# LP55231_breakout.net
KiCad netlist of a schematic drawn in EAGLE
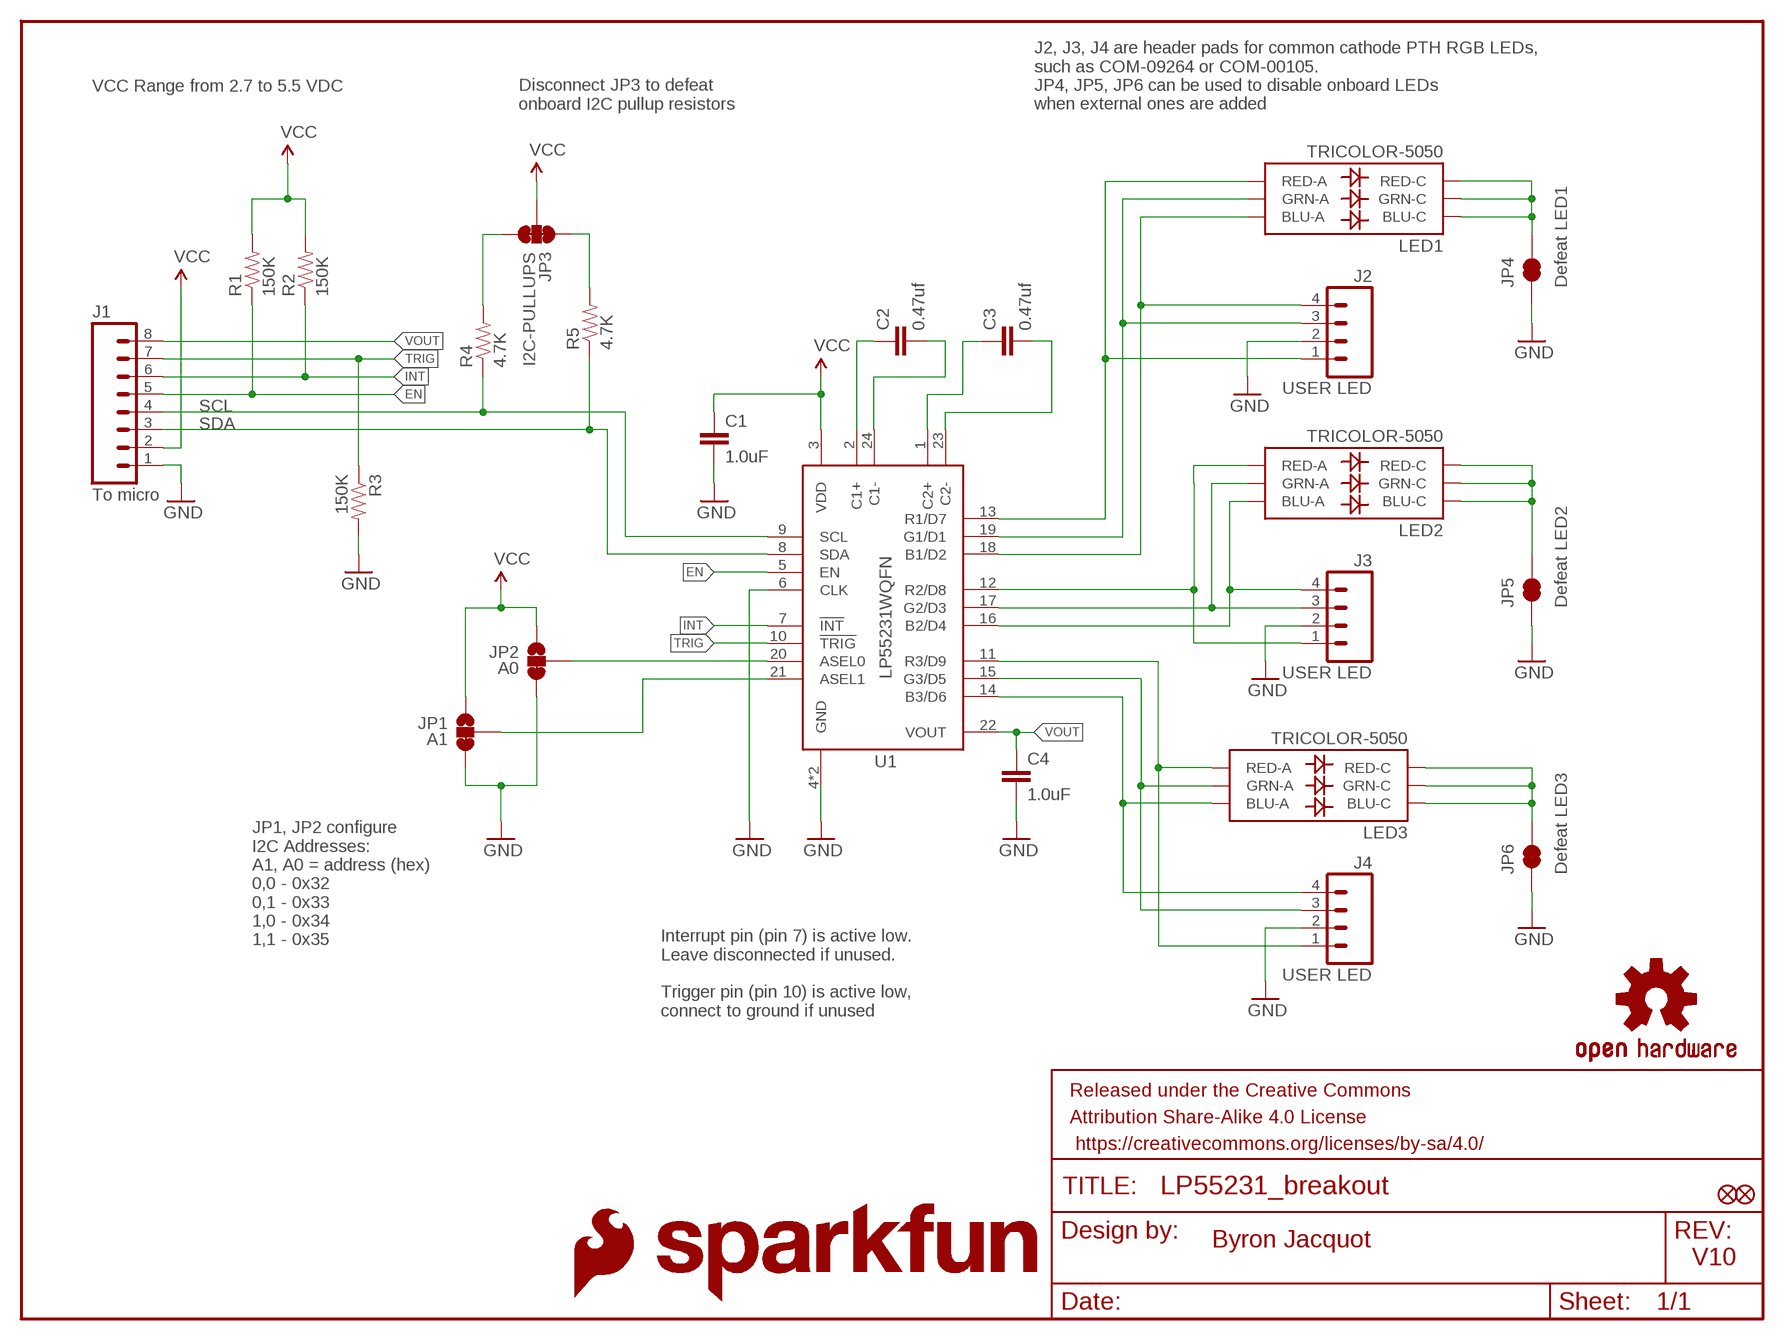
[diagram p0: schematic, sheet 1]

(export (version "E")
  (design (tool "Eeschema 10.0.6"))
  (components
    (comp (ref "C1")
      (value "1.0uF")
      (footprint "eagle-import:0603-CAP")
      (libsource (lib "eagle-import") (part "1.0UF-16V-10%(0603)"))
    )
    (comp (ref "C2")
      (value "0.47uf")
      (footprint "eagle-import:0603-CAP")
      (libsource (lib "eagle-import") (part "CAP0603-CAP"))
    )
    (comp (ref "C3")
      (value "0.47uf")
      (footprint "eagle-import:0603-CAP")
      (libsource (lib "eagle-import") (part "CAP0603-CAP"))
    )
    (comp (ref "C4")
      (value "1.0uF")
      (footprint "eagle-import:0603-CAP")
      (libsource (lib "eagle-import") (part "1.0UF-16V-10%(0603)"))
    )
    (comp (ref "FD1")
      (value "FIDUCIALUFIDUCIAL")
      (footprint "eagle-import:MICRO-FIDUCIAL")
      (libsource (lib "eagle-import") (part "FIDUCIALUFIDUCIAL"))
    )
    (comp (ref "FD2")
      (value "FIDUCIALUFIDUCIAL")
      (footprint "eagle-import:MICRO-FIDUCIAL")
      (libsource (lib "eagle-import") (part "FIDUCIALUFIDUCIAL"))
    )
    (comp (ref "FRAME1")
      (value "FRAME-LETTER")
      (footprint "eagle-import:CREATIVE_COMMONS")
      (libsource (lib "eagle-import") (part "FRAME-LETTER"))
    )
    (comp (ref "J1")
      (value "To micro")
      (footprint "eagle-import:1X08_NO_SILK")
      (libsource (lib "eagle-import") (part "M08NO_SILK_FEMALE_PTH"))
    )
    (comp (ref "J2")
      (value "USER LED")
      (footprint "eagle-import:1X04_NO_SILK_ALL_ROUND")
      (libsource (lib "eagle-import") (part "M04NO_SILK_ALL_ROUND"))
    )
    (comp (ref "J3")
      (value "USER LED")
      (footprint "eagle-import:1X04_NO_SILK_ALL_ROUND")
      (libsource (lib "eagle-import") (part "M04NO_SILK_ALL_ROUND"))
    )
    (comp (ref "J4")
      (value "USER LED")
      (footprint "eagle-import:1X04_NO_SILK_ALL_ROUND")
      (libsource (lib "eagle-import") (part "M04NO_SILK_ALL_ROUND"))
    )
    (comp (ref "JP1")
      (value "A1")
      (footprint "eagle-import:PAD-JUMPER-3-2OF3_NC_BY_TRACE_YES_SILK_FULL_BOX")
      (libsource (lib "eagle-import") (part "JUMPER-PAD-3-2OF3_NC_BY_TRACE_SMALL"))
    )
    (comp (ref "JP2")
      (value "A0")
      (footprint "eagle-import:PAD-JUMPER-3-2OF3_NC_BY_TRACE_YES_SILK_FULL_BOX")
      (libsource (lib "eagle-import") (part "JUMPER-PAD-3-2OF3_NC_BY_TRACE_SMALL"))
    )
    (comp (ref "JP3")
      (value "I2C-PULLUPS")
      (footprint "eagle-import:PAD-JUMPER-3-3OF3_NC_BY_TRACE_YES_SILK_FULL_BOX")
      (libsource (lib "eagle-import") (part "JUMPER-PAD-3-NC_BY_TRACE"))
    )
    (comp (ref "JP4")
      (value "Defeat LED1")
      (footprint "eagle-import:PAD-JUMPER-2-NC_BY_TRACE_NO_SILK")
      (libsource (lib "eagle-import") (part "JUMPER-PAD-2-NC_BY_TRACENO_SILK"))
    )
    (comp (ref "JP5")
      (value "Defeat LED2")
      (footprint "eagle-import:PAD-JUMPER-2-NC_BY_TRACE_NO_SILK")
      (libsource (lib "eagle-import") (part "JUMPER-PAD-2-NC_BY_TRACENO_SILK"))
    )
    (comp (ref "JP6")
      (value "Defeat LED3")
      (footprint "eagle-import:PAD-JUMPER-2-NC_BY_TRACE_NO_SILK")
      (libsource (lib "eagle-import") (part "JUMPER-PAD-2-NC_BY_TRACENO_SILK"))
    )
    (comp (ref "LED1")
      (value "TRICOLOR-5050")
      (footprint "eagle-import:LED-TRICOLOR-5050")
      (libsource (lib "eagle-import") (part "LED-TRICOLOR-5050NO_IC"))
    )
    (comp (ref "LED2")
      (value "TRICOLOR-5050")
      (footprint "eagle-import:LED-TRICOLOR-5050")
      (libsource (lib "eagle-import") (part "LED-TRICOLOR-5050NO_IC"))
    )
    (comp (ref "LED3")
      (value "TRICOLOR-5050")
      (footprint "eagle-import:LED-TRICOLOR-5050")
      (libsource (lib "eagle-import") (part "LED-TRICOLOR-5050NO_IC"))
    )
    (comp (ref "LOGO1")
      (value "SFE_LOGO_FLAME.1_INCH")
      (footprint "eagle-import:SFE_LOGO_FLAME_.1")
      (libsource (lib "eagle-import") (part "SFE_LOGO_FLAME.1_INCH"))
    )
    (comp (ref "LOGO2")
      (value "SFE_LOGO_NAME.1_INCH")
      (footprint "eagle-import:SFE_LOGO_NAME_.1")
      (libsource (lib "eagle-import") (part "SFE_LOGO_NAME.1_INCH"))
    )
    (comp (ref "LOGO3")
      (value "OSHW-LOGOS")
      (footprint "eagle-import:OSHW-LOGO-S")
      (libsource (lib "eagle-import") (part "OSHW-LOGOS"))
    )
    (comp (ref "R1")
      (value "150K")
      (footprint "eagle-import:0603-RES")
      (libsource (lib "eagle-import") (part "150KOHM1/10W1%(0603)"))
    )
    (comp (ref "R2")
      (value "150K")
      (footprint "eagle-import:0603-RES")
      (libsource (lib "eagle-import") (part "150KOHM1/10W1%(0603)"))
    )
    (comp (ref "R3")
      (value "150K")
      (footprint "eagle-import:0603-RES")
      (libsource (lib "eagle-import") (part "150KOHM1/10W1%(0603)"))
    )
    (comp (ref "R4")
      (value "4.7K")
      (footprint "eagle-import:0603-RES")
      (libsource (lib "eagle-import") (part "4.7KOHM-1/10W-1%(0603)"))
    )
    (comp (ref "R5")
      (value "4.7K")
      (footprint "eagle-import:0603-RES")
      (libsource (lib "eagle-import") (part "4.7KOHM-1/10W-1%(0603)"))
    )
    (comp (ref "U1")
      (value "LP55231WQFN")
      (footprint "eagle-import:WQFN-24")
      (libsource (lib "eagle-import") (part "LP55231WQFN"))
    )
  )
  (nets
    (net (code "1") (name "/SCL") (class "Default")
      (node (ref "J1") (pin "4") (pinfunction "4_4") (pintype "passive"))
      (node (ref "R4") (pin "1") (pinfunction "1_1") (pintype "passive"))
      (node (ref "U1") (pin "9") (pinfunction "SCL_9") (pintype "bidirectional"))
    )
    (net (code "2") (name "/SDA") (class "Default")
      (node (ref "J1") (pin "3") (pinfunction "3_3") (pintype "passive"))
      (node (ref "R5") (pin "1") (pinfunction "1_1") (pintype "passive"))
      (node (ref "U1") (pin "8") (pinfunction "SDA_8") (pintype "bidirectional"))
    )
    (net (code "3") (name "EN") (class "Default")
      (node (ref "J1") (pin "5") (pinfunction "5_5") (pintype "passive"))
      (node (ref "R1") (pin "1") (pinfunction "1_1") (pintype "passive"))
      (node (ref "U1") (pin "5") (pinfunction "EN_5") (pintype "bidirectional"))
    )
    (net (code "4") (name "GND") (class "Default")
      (node (ref "C1") (pin "2") (pinfunction "2_2") (pintype "passive"))
      (node (ref "C4") (pin "2") (pinfunction "2_2") (pintype "passive"))
      (node (ref "J1") (pin "1") (pinfunction "1_1") (pintype "passive"))
      (node (ref "J2") (pin "2") (pinfunction "2_2") (pintype "passive"))
      (node (ref "J3") (pin "2") (pinfunction "2_2") (pintype "passive"))
      (node (ref "J4") (pin "2") (pinfunction "2_2") (pintype "passive"))
      (node (ref "JP1") (pin "3") (pinfunction "3_3") (pintype "passive"))
      (node (ref "JP2") (pin "3") (pinfunction "3_3") (pintype "passive"))
      (node (ref "JP4") (pin "1") (pinfunction "1_1") (pintype "passive"))
      (node (ref "JP5") (pin "1") (pinfunction "1_1") (pintype "passive"))
      (node (ref "JP6") (pin "1") (pinfunction "1_1") (pintype "passive"))
      (node (ref "R3") (pin "2") (pinfunction "2_2") (pintype "passive"))
      (node (ref "U1") (pin "4") (pinfunction "GND_4") (pintype "bidirectional"))
      (node (ref "U1") (pin "6") (pinfunction "CLK_6") (pintype "bidirectional"))
      (node (ref "U1") (pin "EP") (pinfunction "GND_EP") (pintype "bidirectional"))
    )
    (net (code "5") (name "INT") (class "Default")
      (node (ref "J1") (pin "6") (pinfunction "6_6") (pintype "passive"))
      (node (ref "R2") (pin "1") (pinfunction "1_1") (pintype "passive"))
      (node (ref "U1") (pin "7") (pinfunction "~{INT}_7") (pintype "bidirectional"))
    )
    (net (code "6") (name "Net-(JP3-Pad1)") (class "Default")
      (node (ref "JP3") (pin "1") (pinfunction "1_1") (pintype "passive"))
      (node (ref "R5") (pin "2") (pinfunction "2_2") (pintype "passive"))
    )
    (net (code "7") (name "Net-(JP3-Pad3)") (class "Default")
      (node (ref "JP3") (pin "3") (pinfunction "3_3") (pintype "passive"))
      (node (ref "R4") (pin "2") (pinfunction "2_2") (pintype "passive"))
    )
    (net (code "8") (name "Net-(LED1-BLU-A)") (class "Default")
      (node (ref "J2") (pin "4") (pinfunction "4_4") (pintype "passive"))
      (node (ref "LED1") (pin "3") (pinfunction "BLU-A_3") (pintype "bidirectional"))
      (node (ref "U1") (pin "18") (pinfunction "B1/D2_18") (pintype "bidirectional"))
    )
    (net (code "9") (name "Net-(LED1-BLU-C)") (class "Default")
      (node (ref "JP4") (pin "2") (pinfunction "2_2") (pintype "passive"))
      (node (ref "LED1") (pin "4") (pinfunction "BLU-C_4") (pintype "bidirectional"))
      (node (ref "LED1") (pin "5") (pinfunction "RED-C_5") (pintype "bidirectional"))
      (node (ref "LED1") (pin "6") (pinfunction "GRN-C_6") (pintype "bidirectional"))
    )
    (net (code "10") (name "Net-(LED1-GRN-A)") (class "Default")
      (node (ref "J2") (pin "3") (pinfunction "3_3") (pintype "passive"))
      (node (ref "LED1") (pin "1") (pinfunction "GRN-A_1") (pintype "bidirectional"))
      (node (ref "U1") (pin "19") (pinfunction "G1/D1_19") (pintype "bidirectional"))
    )
    (net (code "11") (name "Net-(LED1-RED-A)") (class "Default")
      (node (ref "J2") (pin "1") (pinfunction "1_1") (pintype "passive"))
      (node (ref "LED1") (pin "2") (pinfunction "RED-A_2") (pintype "bidirectional"))
      (node (ref "U1") (pin "13") (pinfunction "R1/D7_13") (pintype "bidirectional"))
    )
    (net (code "12") (name "Net-(LED2-BLU-A)") (class "Default")
      (node (ref "J3") (pin "4") (pinfunction "4_4") (pintype "passive"))
      (node (ref "LED2") (pin "3") (pinfunction "BLU-A_3") (pintype "bidirectional"))
      (node (ref "U1") (pin "16") (pinfunction "B2/D4_16") (pintype "bidirectional"))
    )
    (net (code "13") (name "Net-(LED2-BLU-C)") (class "Default")
      (node (ref "JP5") (pin "2") (pinfunction "2_2") (pintype "passive"))
      (node (ref "LED2") (pin "4") (pinfunction "BLU-C_4") (pintype "bidirectional"))
      (node (ref "LED2") (pin "5") (pinfunction "RED-C_5") (pintype "bidirectional"))
      (node (ref "LED2") (pin "6") (pinfunction "GRN-C_6") (pintype "bidirectional"))
    )
    (net (code "14") (name "Net-(LED2-GRN-A)") (class "Default")
      (node (ref "J3") (pin "3") (pinfunction "3_3") (pintype "passive"))
      (node (ref "LED2") (pin "1") (pinfunction "GRN-A_1") (pintype "bidirectional"))
      (node (ref "U1") (pin "17") (pinfunction "G2/D3_17") (pintype "bidirectional"))
    )
    (net (code "15") (name "Net-(LED2-RED-A)") (class "Default")
      (node (ref "J3") (pin "1") (pinfunction "1_1") (pintype "passive"))
      (node (ref "LED2") (pin "2") (pinfunction "RED-A_2") (pintype "bidirectional"))
      (node (ref "U1") (pin "12") (pinfunction "R2/D8_12") (pintype "bidirectional"))
    )
    (net (code "16") (name "Net-(LED3-BLU-A)") (class "Default")
      (node (ref "J4") (pin "4") (pinfunction "4_4") (pintype "passive"))
      (node (ref "LED3") (pin "3") (pinfunction "BLU-A_3") (pintype "bidirectional"))
      (node (ref "U1") (pin "14") (pinfunction "B3/D6_14") (pintype "bidirectional"))
    )
    (net (code "17") (name "Net-(LED3-BLU-C)") (class "Default")
      (node (ref "JP6") (pin "2") (pinfunction "2_2") (pintype "passive"))
      (node (ref "LED3") (pin "4") (pinfunction "BLU-C_4") (pintype "bidirectional"))
      (node (ref "LED3") (pin "5") (pinfunction "RED-C_5") (pintype "bidirectional"))
      (node (ref "LED3") (pin "6") (pinfunction "GRN-C_6") (pintype "bidirectional"))
    )
    (net (code "18") (name "Net-(LED3-GRN-A)") (class "Default")
      (node (ref "J4") (pin "3") (pinfunction "3_3") (pintype "passive"))
      (node (ref "LED3") (pin "1") (pinfunction "GRN-A_1") (pintype "bidirectional"))
      (node (ref "U1") (pin "15") (pinfunction "G3/D5_15") (pintype "bidirectional"))
    )
    (net (code "19") (name "Net-(LED3-RED-A)") (class "Default")
      (node (ref "J4") (pin "1") (pinfunction "1_1") (pintype "passive"))
      (node (ref "LED3") (pin "2") (pinfunction "RED-A_2") (pintype "bidirectional"))
      (node (ref "U1") (pin "11") (pinfunction "R3/D9_11") (pintype "bidirectional"))
    )
    (net (code "20") (name "Net-(U1-ASEL0)") (class "Default")
      (node (ref "JP2") (pin "2") (pinfunction "2_2") (pintype "passive"))
      (node (ref "U1") (pin "20") (pinfunction "ASEL0_20") (pintype "bidirectional"))
    )
    (net (code "21") (name "Net-(U1-ASEL1)") (class "Default")
      (node (ref "JP1") (pin "2") (pinfunction "2_2") (pintype "passive"))
      (node (ref "U1") (pin "21") (pinfunction "ASEL1_21") (pintype "bidirectional"))
    )
    (net (code "22") (name "Net-(U1-C1+)") (class "Default")
      (node (ref "C2") (pin "1") (pinfunction "1_1") (pintype "passive"))
      (node (ref "U1") (pin "2") (pinfunction "C1+_2") (pintype "bidirectional"))
    )
    (net (code "23") (name "Net-(U1-C1-)") (class "Default")
      (node (ref "C2") (pin "2") (pinfunction "2_2") (pintype "passive"))
      (node (ref "U1") (pin "24") (pinfunction "C1-_24") (pintype "bidirectional"))
    )
    (net (code "24") (name "Net-(U1-C2+)") (class "Default")
      (node (ref "C3") (pin "1") (pinfunction "1_1") (pintype "passive"))
      (node (ref "U1") (pin "1") (pinfunction "C2+_1") (pintype "bidirectional"))
    )
    (net (code "25") (name "Net-(U1-C2-)") (class "Default")
      (node (ref "C3") (pin "2") (pinfunction "2_2") (pintype "passive"))
      (node (ref "U1") (pin "23") (pinfunction "C2-_23") (pintype "bidirectional"))
    )
    (net (code "26") (name "TRIG") (class "Default")
      (node (ref "J1") (pin "7") (pinfunction "7_7") (pintype "passive"))
      (node (ref "R3") (pin "1") (pinfunction "1_1") (pintype "passive"))
      (node (ref "U1") (pin "10") (pinfunction "~{TRIG}_10") (pintype "bidirectional"))
    )
    (net (code "27") (name "VCC") (class "Default")
      (node (ref "C1") (pin "1") (pinfunction "1_1") (pintype "passive"))
      (node (ref "J1") (pin "2") (pinfunction "2_2") (pintype "passive"))
      (node (ref "JP1") (pin "1") (pinfunction "1_1") (pintype "passive"))
      (node (ref "JP2") (pin "1") (pinfunction "1_1") (pintype "passive"))
      (node (ref "JP3") (pin "2") (pinfunction "2_2") (pintype "passive"))
      (node (ref "R1") (pin "2") (pinfunction "2_2") (pintype "passive"))
      (node (ref "R2") (pin "2") (pinfunction "2_2") (pintype "passive"))
      (node (ref "U1") (pin "3") (pinfunction "VDD_3") (pintype "bidirectional"))
    )
    (net (code "28") (name "VOUT") (class "Default")
      (node (ref "C4") (pin "1") (pinfunction "1_1") (pintype "passive"))
      (node (ref "J1") (pin "8") (pinfunction "8_8") (pintype "passive"))
      (node (ref "U1") (pin "22") (pinfunction "VOUT_22") (pintype "bidirectional"))
    )
  )
)
